# source_eagle.net
KiCad netlist of a schematic drawn in EAGLE
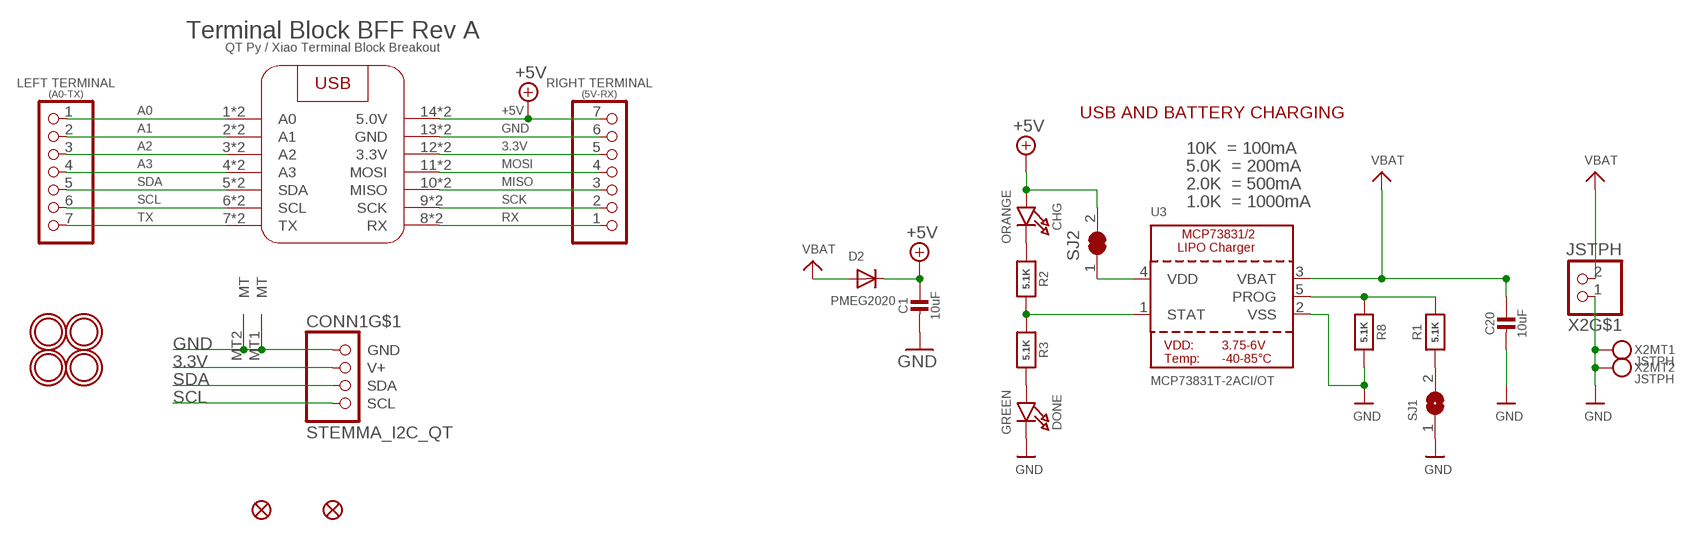
[diagram p0: schematic, sheet 1]

(export (version "E")
  (design (tool "Eeschema 10.0.6"))
  (components
    (comp (ref "C1")
      (value "10uF")
      (footprint "eagle-import:0805-NO")
      (libsource (lib "eagle-import") (part "CAP_CERAMIC0805-NOOUTLINE"))
    )
    (comp (ref "C20")
      (value "10uF")
      (footprint "eagle-import:0805-NO")
      (libsource (lib "eagle-import") (part "CAP_CERAMIC0805-NOOUTLINE"))
    )
    (comp (ref "CHG")
      (value "ORANGE")
      (footprint "eagle-import:CHIPLED_0603_NOOUTLINE")
      (libsource (lib "eagle-import") (part "LED0603_NOOUTLINE"))
    )
    (comp (ref "CONN1")
      (value "STEMMA_I2C_QT")
      (footprint "eagle-import:JST_SH4")
      (libsource (lib "eagle-import") (part "STEMMA_I2C_QT"))
    )
    (comp (ref "D2")
      (value "PMEG2020")
      (footprint "eagle-import:SOD-123FL")
      (libsource (lib "eagle-import") (part "DIODE_SOD-123FL"))
    )
    (comp (ref "DONE")
      (value "GREEN")
      (footprint "eagle-import:CHIPLED_0603_NOOUTLINE")
      (libsource (lib "eagle-import") (part "LED0603_NOOUTLINE"))
    )
    (comp (ref "FID1")
      (value "FIDUCIAL_0.5MM")
      (footprint "eagle-import:FIDUCIAL_0.5MM")
      (libsource (lib "eagle-import") (part "FIDUCIAL_0.5MM"))
    )
    (comp (ref "FID2")
      (value "FIDUCIAL_0.5MM")
      (footprint "eagle-import:FIDUCIAL_0.5MM")
      (libsource (lib "eagle-import") (part "FIDUCIAL_0.5MM"))
    )
    (comp (ref "JP1")
      (value "Terminal")
      (footprint "eagle-import:1X07_2.54MMTERMINAL")
      (libsource (lib "eagle-import") (part "HEADER-1X7_2.54MMTERM"))
    )
    (comp (ref "JP2")
      (value "Terminal")
      (footprint "eagle-import:1X07_2.54MMTERMINAL")
      (libsource (lib "eagle-import") (part "HEADER-1X7_2.54MMTERM"))
    )
    (comp (ref "R1")
      (value "5.1K")
      (footprint "eagle-import:_0402NO")
      (libsource (lib "eagle-import") (part "RESISTOR_0402NO"))
    )
    (comp (ref "R2")
      (value "5.1K")
      (footprint "eagle-import:_0402NO")
      (libsource (lib "eagle-import") (part "RESISTOR_0402NO"))
    )
    (comp (ref "R3")
      (value "5.1K")
      (footprint "eagle-import:_0402NO")
      (libsource (lib "eagle-import") (part "RESISTOR_0402NO"))
    )
    (comp (ref "R8")
      (value "5.1K")
      (footprint "eagle-import:_0402NO")
      (libsource (lib "eagle-import") (part "RESISTOR_0402NO"))
    )
    (comp (ref "SJ1")
      (value "SOLDERJUMPER")
      (footprint "eagle-import:SOLDERJUMPER_ARROW_NOPASTE")
      (libsource (lib "eagle-import") (part "SOLDERJUMPER"))
    )
    (comp (ref "SJ2")
      (value "SOLDERJUMPER_CLOSED")
      (footprint "eagle-import:SOLDERJUMPER_CLOSEDWIRE")
      (libsource (lib "eagle-import") (part "SOLDERJUMPER_CLOSED"))
    )
    (comp (ref "U$1")
      (value "MOUNTINGHOLE2.5")
      (footprint "eagle-import:MOUNTINGHOLE_2.5_PLATED")
      (libsource (lib "eagle-import") (part "MOUNTINGHOLE2.5"))
    )
    (comp (ref "U$2")
      (value "MOUNTINGHOLE2.5")
      (footprint "eagle-import:MOUNTINGHOLE_2.5_PLATED")
      (libsource (lib "eagle-import") (part "MOUNTINGHOLE2.5"))
    )
    (comp (ref "U$3")
      (value "MOUNTINGHOLE2.5")
      (footprint "eagle-import:MOUNTINGHOLE_2.5_PLATED")
      (libsource (lib "eagle-import") (part "MOUNTINGHOLE2.5"))
    )
    (comp (ref "U$4")
      (value "MOUNTINGHOLE2.5")
      (footprint "eagle-import:MOUNTINGHOLE_2.5_PLATED")
      (libsource (lib "eagle-import") (part "MOUNTINGHOLE2.5"))
    )
    (comp (ref "U3")
      (value "MCP73831T-2ACI/OT")
      (footprint "eagle-import:SOT23-5")
      (libsource (lib "eagle-import") (part "MCP73831/2"))
    )
    (comp (ref "X1")
      (value "QTPY_SOCKET_DUAL_SMT")
      (footprint "eagle-import:QTPY_SMT")
      (libsource (lib "eagle-import") (part "QTPY_SOCKET_DUAL_SMT"))
    )
    (comp (ref "X2")
      (value "JSTPH")
      (footprint "eagle-import:JSTPH2_BATT")
      (libsource (lib "eagle-import") (part "CON_JST_PH_2PIN_MT_BATT"))
    )
  )
  (nets
    (net (code "1") (name "+5V") (class "Default")
      (node (ref "C1") (pin "1") (pinfunction "1_1") (pintype "passive"))
      (node (ref "CHG") (pin "A") (pinfunction "A_A") (pintype "passive"))
      (node (ref "D2") (pin "C") (pinfunction "C_C") (pintype "passive"))
      (node (ref "JP1") (pin "7") (pinfunction "7_7") (pintype "passive"))
      (node (ref "SJ2") (pin "2") (pinfunction "2_2") (pintype "passive"))
      (node (ref "X1") (pin "14") (pinfunction "5.0V_14") (pintype "power_in"))
      (node (ref "X1") (pin "14B") (pinfunction "5.0V_14B") (pintype "power_in"))
    )
    (net (code "2") (name "/3.3V") (class "Default")
      (node (ref "CONN1") (pin "2") (pinfunction "V+_2") (pintype "passive"))
      (node (ref "JP1") (pin "5") (pinfunction "5_5") (pintype "passive"))
      (node (ref "X1") (pin "12") (pinfunction "3.3V_12") (pintype "power_in"))
      (node (ref "X1") (pin "12B") (pinfunction "3.3V_12B") (pintype "power_in"))
    )
    (net (code "3") (name "/A0") (class "Default")
      (node (ref "JP2") (pin "1") (pinfunction "1_1") (pintype "passive"))
      (node (ref "X1") (pin "1") (pinfunction "A0_1") (pintype "bidirectional"))
      (node (ref "X1") (pin "1B") (pinfunction "A0_1B") (pintype "bidirectional"))
    )
    (net (code "4") (name "/A1") (class "Default")
      (node (ref "JP2") (pin "2") (pinfunction "2_2") (pintype "passive"))
      (node (ref "X1") (pin "2") (pinfunction "A1_2") (pintype "bidirectional"))
      (node (ref "X1") (pin "2B") (pinfunction "A1_2B") (pintype "bidirectional"))
    )
    (net (code "5") (name "/A2") (class "Default")
      (node (ref "JP2") (pin "3") (pinfunction "3_3") (pintype "passive"))
      (node (ref "X1") (pin "3") (pinfunction "A2_3") (pintype "bidirectional"))
      (node (ref "X1") (pin "3B") (pinfunction "A2_3B") (pintype "bidirectional"))
    )
    (net (code "6") (name "/A3") (class "Default")
      (node (ref "JP2") (pin "4") (pinfunction "4_4") (pintype "passive"))
      (node (ref "X1") (pin "4") (pinfunction "A3_4") (pintype "bidirectional"))
      (node (ref "X1") (pin "4B") (pinfunction "A3_4B") (pintype "bidirectional"))
    )
    (net (code "7") (name "/MISO") (class "Default")
      (node (ref "JP1") (pin "3") (pinfunction "3_3") (pintype "passive"))
      (node (ref "X1") (pin "10") (pinfunction "MISO_10") (pintype "bidirectional"))
      (node (ref "X1") (pin "10B") (pinfunction "MISO_10B") (pintype "bidirectional"))
    )
    (net (code "8") (name "/MOSI") (class "Default")
      (node (ref "JP1") (pin "4") (pinfunction "4_4") (pintype "passive"))
      (node (ref "X1") (pin "11") (pinfunction "MOSI_11") (pintype "bidirectional"))
      (node (ref "X1") (pin "11B") (pinfunction "MOSI_11B") (pintype "bidirectional"))
    )
    (net (code "9") (name "/RX") (class "Default")
      (node (ref "JP1") (pin "1") (pinfunction "1_1") (pintype "passive"))
      (node (ref "X1") (pin "8") (pinfunction "RX_8") (pintype "bidirectional"))
      (node (ref "X1") (pin "8B") (pinfunction "RX_8B") (pintype "bidirectional"))
    )
    (net (code "10") (name "/SCK") (class "Default")
      (node (ref "JP1") (pin "2") (pinfunction "2_2") (pintype "passive"))
      (node (ref "X1") (pin "9") (pinfunction "SCK_9") (pintype "bidirectional"))
      (node (ref "X1") (pin "9B") (pinfunction "SCK_9B") (pintype "bidirectional"))
    )
    (net (code "11") (name "/SCL") (class "Default")
      (node (ref "CONN1") (pin "4") (pinfunction "SCL_4") (pintype "passive"))
      (node (ref "JP2") (pin "6") (pinfunction "6_6") (pintype "passive"))
      (node (ref "X1") (pin "6") (pinfunction "SCL_6") (pintype "bidirectional"))
      (node (ref "X1") (pin "6B") (pinfunction "SCL_6B") (pintype "bidirectional"))
    )
    (net (code "12") (name "/SDA") (class "Default")
      (node (ref "CONN1") (pin "3") (pinfunction "SDA_3") (pintype "passive"))
      (node (ref "JP2") (pin "5") (pinfunction "5_5") (pintype "passive"))
      (node (ref "X1") (pin "5") (pinfunction "SDA_5") (pintype "bidirectional"))
      (node (ref "X1") (pin "5B") (pinfunction "SDA_5B") (pintype "bidirectional"))
    )
    (net (code "13") (name "/TX") (class "Default")
      (node (ref "JP2") (pin "7") (pinfunction "7_7") (pintype "passive"))
      (node (ref "X1") (pin "7") (pinfunction "TX_7") (pintype "bidirectional"))
      (node (ref "X1") (pin "7B") (pinfunction "TX_7B") (pintype "bidirectional"))
    )
    (net (code "14") (name "GND") (class "Default")
      (node (ref "C1") (pin "2") (pinfunction "2_2") (pintype "passive"))
      (node (ref "C20") (pin "2") (pinfunction "2_2") (pintype "passive"))
      (node (ref "CONN1") (pin "1") (pinfunction "GND_1") (pintype "passive"))
      (node (ref "CONN1") (pin "MT1") (pinfunction "MT_MT1") (pintype "bidirectional"))
      (node (ref "CONN1") (pin "MT2") (pinfunction "MT_MT2") (pintype "bidirectional"))
      (node (ref "DONE") (pin "C") (pinfunction "C_C") (pintype "passive"))
      (node (ref "JP1") (pin "6") (pinfunction "6_6") (pintype "passive"))
      (node (ref "R8") (pin "2") (pinfunction "2_2") (pintype "passive"))
      (node (ref "SJ1") (pin "1") (pinfunction "1_1") (pintype "passive"))
      (node (ref "U3") (pin "2") (pinfunction "VSS_2") (pintype "power_in"))
      (node (ref "X1") (pin "13") (pinfunction "GND_13") (pintype "power_in"))
      (node (ref "X1") (pin "13B") (pinfunction "GND_13B") (pintype "power_in"))
      (node (ref "X2") (pin "1") (pinfunction "1_1") (pintype "passive"))
      (node (ref "X2") (pin "NC1") (pinfunction "P$1_NC1") (pintype "bidirectional"))
      (node (ref "X2") (pin "NC2") (pinfunction "P$1_NC2") (pintype "bidirectional"))
    )
    (net (code "15") (name "Net-(CHG-PadC)") (class "Default")
      (node (ref "CHG") (pin "C") (pinfunction "C_C") (pintype "passive"))
      (node (ref "R2") (pin "1") (pinfunction "1_1") (pintype "passive"))
    )
    (net (code "16") (name "Net-(DONE-PadA)") (class "Default")
      (node (ref "DONE") (pin "A") (pinfunction "A_A") (pintype "passive"))
      (node (ref "R3") (pin "2") (pinfunction "2_2") (pintype "passive"))
    )
    (net (code "17") (name "Net-(R1-Pad1)") (class "Default")
      (node (ref "R1") (pin "1") (pinfunction "1_1") (pintype "passive"))
      (node (ref "SJ1") (pin "2") (pinfunction "2_2") (pintype "passive"))
    )
    (net (code "18") (name "Net-(U3-PROG)") (class "Default")
      (node (ref "R1") (pin "2") (pinfunction "2_2") (pintype "passive"))
      (node (ref "R8") (pin "1") (pinfunction "1_1") (pintype "passive"))
      (node (ref "U3") (pin "5") (pinfunction "PROG_5") (pintype "input"))
    )
    (net (code "19") (name "Net-(U3-STAT)") (class "Default")
      (node (ref "R2") (pin "2") (pinfunction "2_2") (pintype "passive"))
      (node (ref "R3") (pin "1") (pinfunction "1_1") (pintype "passive"))
      (node (ref "U3") (pin "1") (pinfunction "STAT_1") (pintype "output"))
    )
    (net (code "20") (name "Net-(U3-VDD)") (class "Default")
      (node (ref "SJ2") (pin "1") (pinfunction "1_1") (pintype "passive"))
      (node (ref "U3") (pin "4") (pinfunction "VDD_4") (pintype "power_in"))
    )
    (net (code "21") (name "VBAT") (class "Default")
      (node (ref "C20") (pin "1") (pinfunction "1_1") (pintype "passive"))
      (node (ref "D2") (pin "A") (pinfunction "A_A") (pintype "passive"))
      (node (ref "U3") (pin "3") (pinfunction "VBAT_3") (pintype "power_in"))
      (node (ref "X2") (pin "2") (pinfunction "2_2") (pintype "passive"))
    )
  )
)
